# SCH_Oscilator2_0_2026-05-03.net
KiCad netlist of a schematic drawn in EasyEDA
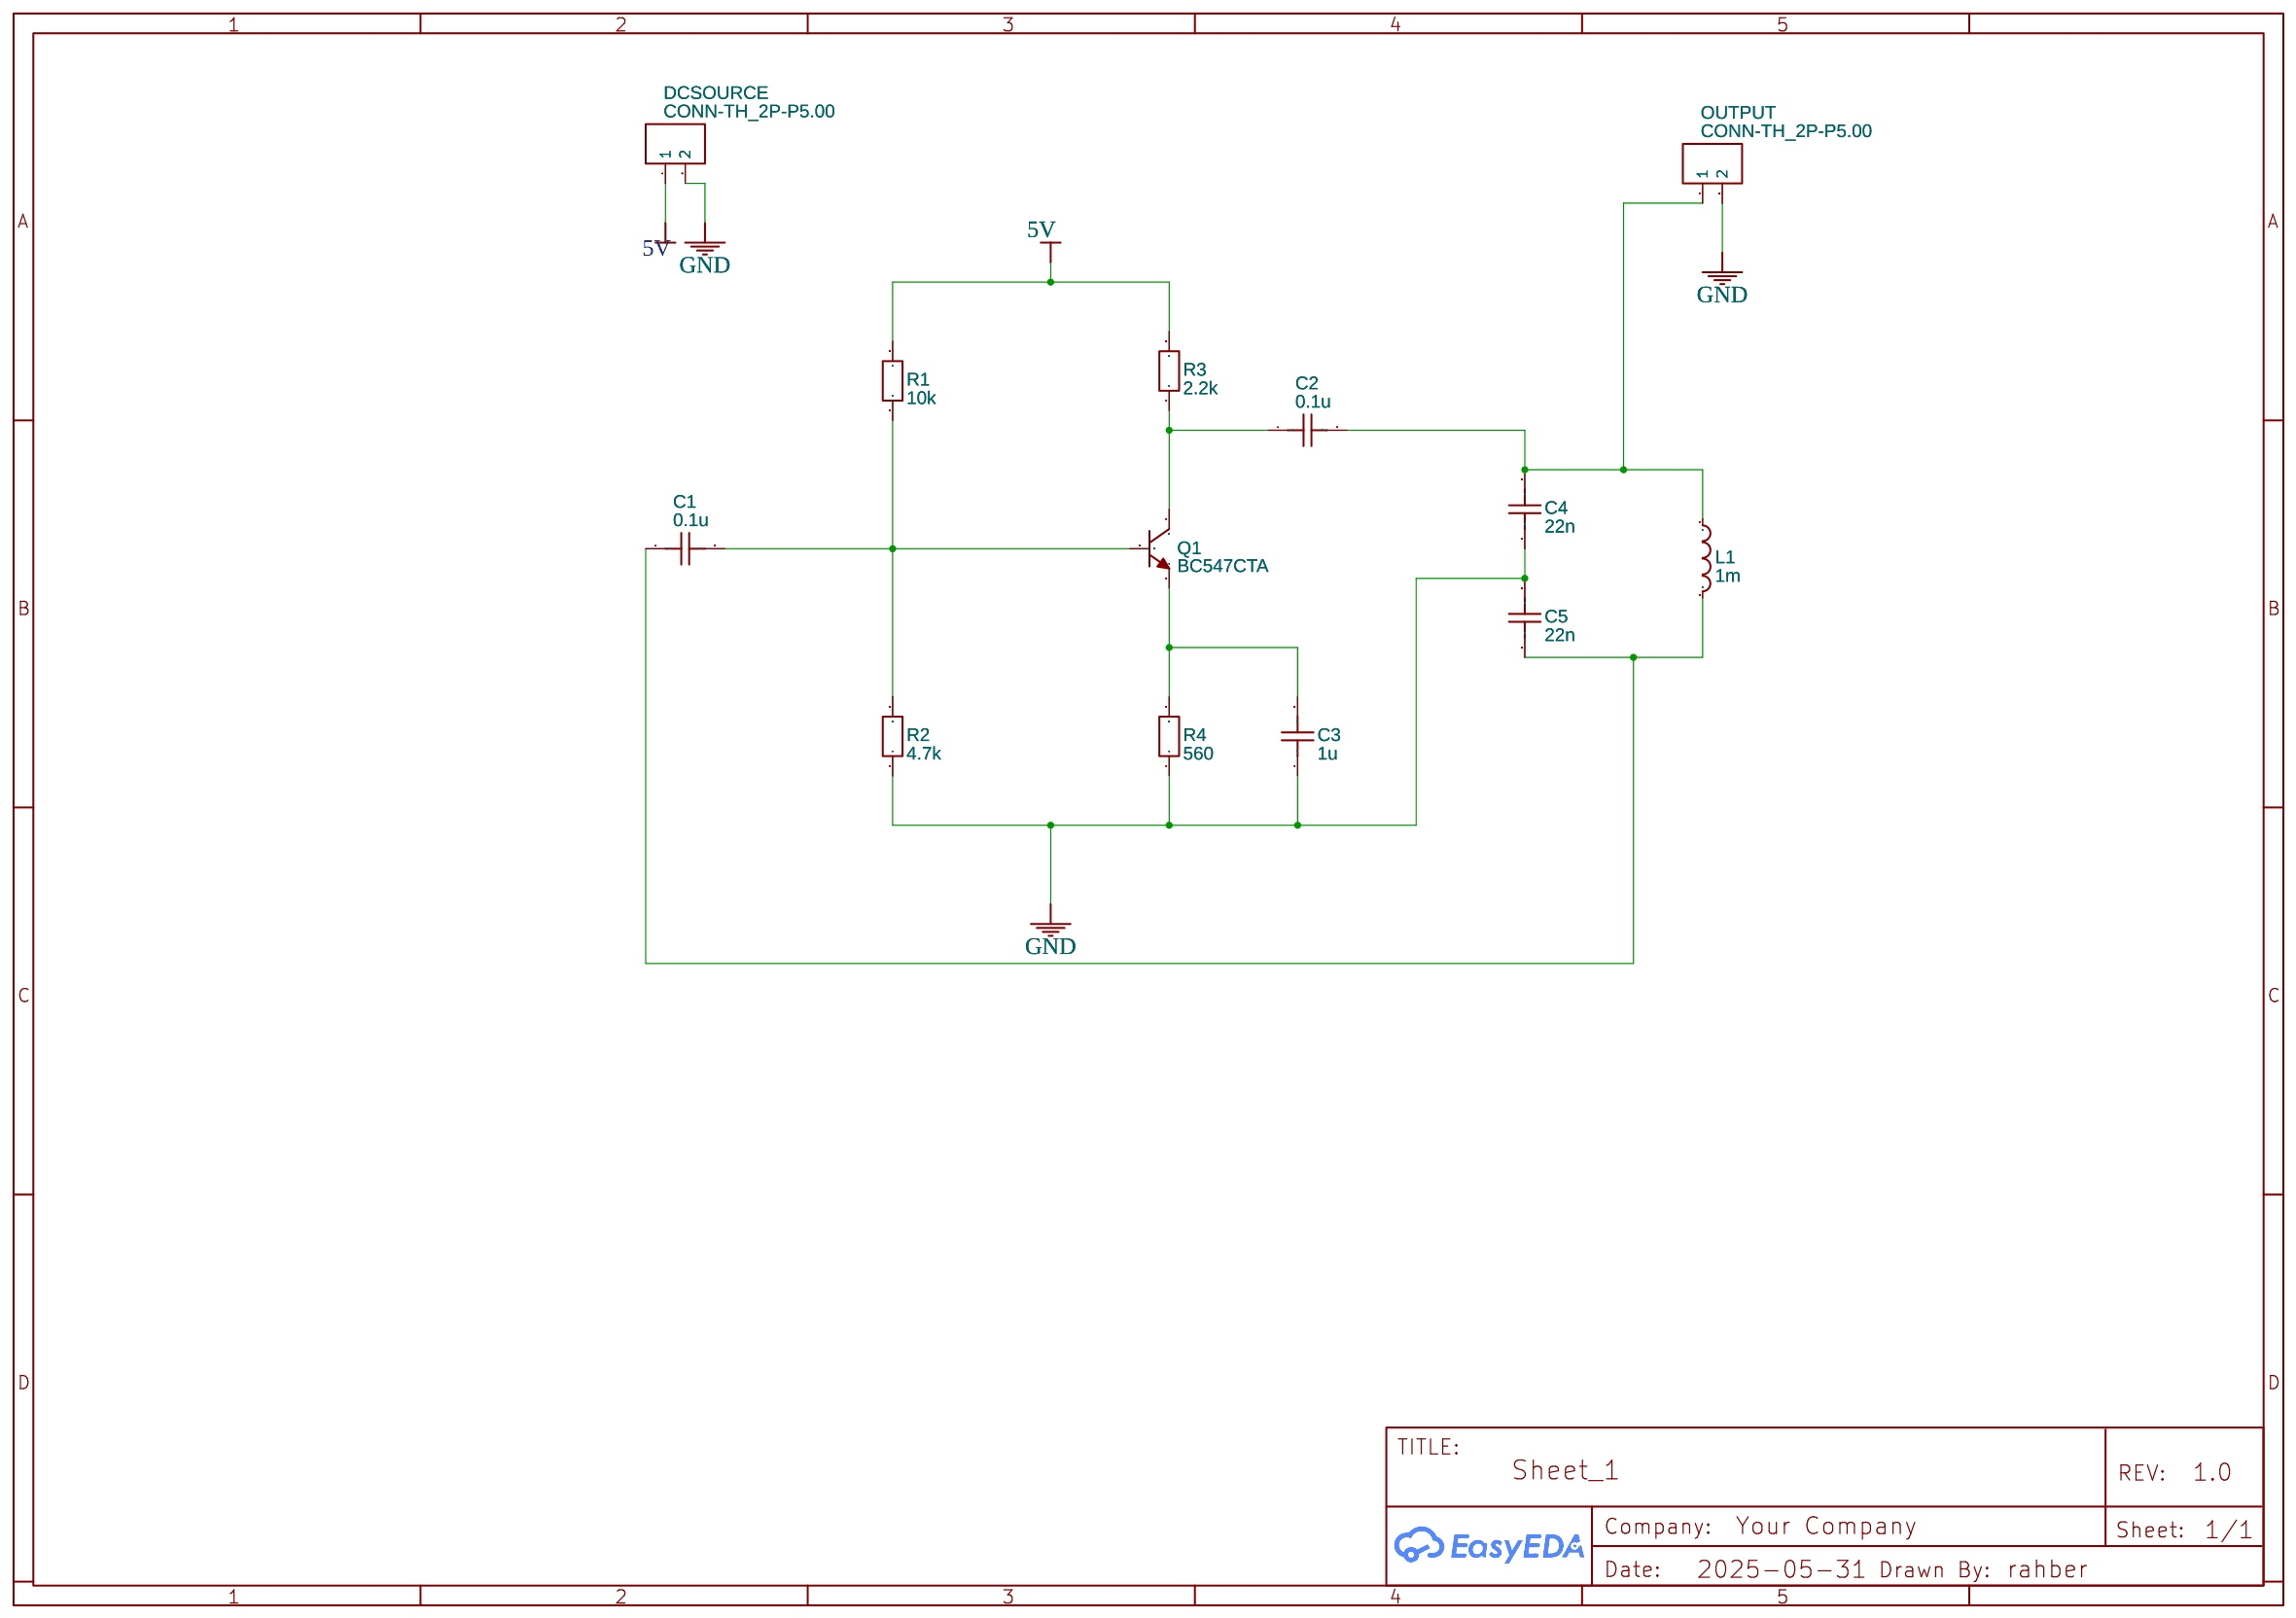
[diagram p0: schematic sheet]

(export (version "E")
  (design (tool "Eeschema 10.0.6"))
  (components
    (comp (ref "C1") (value "0.1u") (libsource (lib "") (part "C_RAD-0.1_US")))
    (comp (ref "C2") (value "0.1u") (libsource (lib "") (part "C_RAD-0.1_US")))
    (comp (ref "C3") (value "1u") (libsource (lib "") (part "C_RAD-0.1_US_1")))
    (comp (ref "C4") (value "22n") (libsource (lib "") (part "C_RAD-0.1_US_1")))
    (comp (ref "C5") (value "22n") (libsource (lib "") (part "C_RAD-0.1_US_1")))
    (comp (ref "DCSOURCE") (value "CONN-TH_2P-P5.00") (libsource (lib "") (part "CONN-TH_2P-P5.00_1")))
    (comp (ref "L1") (value "1m") (libsource (lib "") (part "L_AXIAL-0.4_US")))
    (comp (ref "OUTPUT") (value "CONN-TH_2P-P5.00") (libsource (lib "") (part "CONN-TH_2P-P5.00")))
    (comp (ref "Q1")
      (value "BC547CTA")
      (fields (field (name "Manufacturer") "onsemi(安森美)"))
      (libsource (lib "") (part "BC547CTA"))
    )
    (comp (ref "R1") (value "10k") (libsource (lib "") (part "R_AXIAL-0.5_EU")))
    (comp (ref "R2") (value "4.7k") (libsource (lib "") (part "R_AXIAL-0.5_EU")))
    (comp (ref "R3") (value "2.2k") (libsource (lib "") (part "R_AXIAL-0.5_EU")))
    (comp (ref "R4") (value "560") (libsource (lib "") (part "R_AXIAL-0.5_EU")))
  )
  (nets
    (net (code "1") (name "5V") (class "Default")
      (node (ref "DCSOURCE") (pin "1") (pinfunction "1_1") (pintype "unspecified"))
      (node (ref "R1") (pin "2") (pinfunction "2_2") (pintype "unspecified"))
      (node (ref "R3") (pin "2") (pinfunction "2_2") (pintype "unspecified"))
    )
    (net (code "2") (name "GND") (class "Default")
      (node (ref "C3") (pin "1") (pinfunction "1_1") (pintype "unspecified"))
      (node (ref "C4") (pin "1") (pinfunction "1_1") (pintype "unspecified"))
      (node (ref "C5") (pin "2") (pinfunction "2_2") (pintype "unspecified"))
      (node (ref "DCSOURCE") (pin "2") (pinfunction "2_2") (pintype "unspecified"))
      (node (ref "OUTPUT") (pin "2") (pinfunction "2_2") (pintype "unspecified"))
      (node (ref "R2") (pin "1") (pinfunction "1_1") (pintype "unspecified"))
      (node (ref "R4") (pin "1") (pinfunction "1_1") (pintype "unspecified"))
    )
    (net (code "3") (name "Net-(C1-Pad1)") (class "Default")
      (node (ref "C1") (pin "1") (pinfunction "1_1") (pintype "unspecified"))
      (node (ref "C5") (pin "1") (pinfunction "1_1") (pintype "unspecified"))
      (node (ref "L1") (pin "2") (pinfunction "2_2") (pintype "unspecified"))
    )
    (net (code "4") (name "Net-(C2-Pad2)") (class "Default")
      (node (ref "C2") (pin "2") (pinfunction "2_2") (pintype "unspecified"))
      (node (ref "C4") (pin "2") (pinfunction "2_2") (pintype "unspecified"))
      (node (ref "L1") (pin "1") (pinfunction "1_1") (pintype "unspecified"))
      (node (ref "OUTPUT") (pin "1") (pinfunction "1_1") (pintype "unspecified"))
    )
    (net (code "5") (name "Net-(Q1-B)") (class "Default")
      (node (ref "C1") (pin "2") (pinfunction "2_2") (pintype "unspecified"))
      (node (ref "Q1") (pin "2") (pinfunction "B_2") (pintype "input"))
      (node (ref "R1") (pin "1") (pinfunction "1_1") (pintype "unspecified"))
      (node (ref "R2") (pin "2") (pinfunction "2_2") (pintype "unspecified"))
    )
    (net (code "6") (name "Net-(Q1-C)") (class "Default")
      (node (ref "C2") (pin "1") (pinfunction "1_1") (pintype "unspecified"))
      (node (ref "Q1") (pin "1") (pinfunction "C_1") (pintype "input"))
      (node (ref "R3") (pin "1") (pinfunction "1_1") (pintype "unspecified"))
    )
    (net (code "7") (name "Net-(Q1-E)") (class "Default")
      (node (ref "C3") (pin "2") (pinfunction "2_2") (pintype "unspecified"))
      (node (ref "Q1") (pin "3") (pinfunction "E_3") (pintype "input"))
      (node (ref "R4") (pin "2") (pinfunction "2_2") (pintype "unspecified"))
    )
  )
)
